# project_github.net
KiCad netlist of a schematic drawn in EAGLE
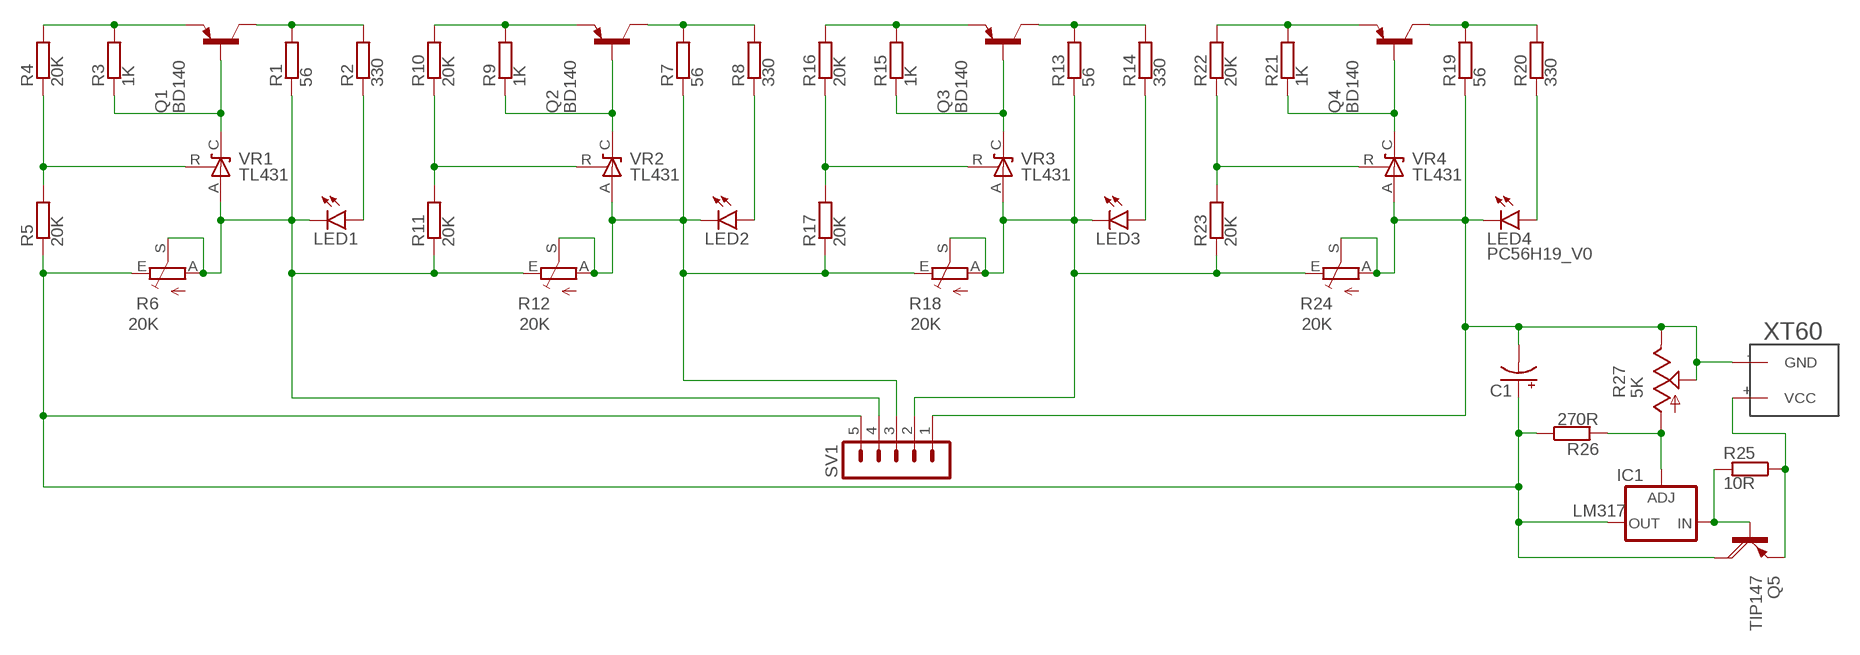
[diagram p0: schematic, sheet 1]

(export (version "E")
  (design (tool "Eeschema 10.0.6"))
  (components
    (comp (ref "C1")
      (value "CPOL-US153CLV-0810")
      (footprint "eagle-import:153CLV-0810")
      (libsource (lib "eagle-import") (part "CPOL-US153CLV-0810"))
    )
    (comp (ref "IC1")
      (value "LM317")
      (footprint "eagle-import:DPACK")
      (libsource (lib "eagle-import") (part "v-reg_409_LM317?MABDT"))
    )
    (comp (ref "LED1")
      (value "PC56H19_V0")
      (footprint "eagle-import:PC56H19_V0")
      (libsource (lib "eagle-import") (part "PC56H19_V0"))
    )
    (comp (ref "LED2")
      (value "PC56H19_V0")
      (footprint "eagle-import:PC56H19_V0")
      (libsource (lib "eagle-import") (part "PC56H19_V0"))
    )
    (comp (ref "LED3")
      (value "PC56H19_V0")
      (footprint "eagle-import:PC56H19_V0")
      (libsource (lib "eagle-import") (part "PC56H19_V0"))
    )
    (comp (ref "LED4")
      (value "PC56H19_V0")
      (footprint "eagle-import:PC56H19_V0")
      (libsource (lib "eagle-import") (part "PC56H19_V0"))
    )
    (comp (ref "Q1")
      (value "BD140")
      (footprint "eagle-import:TO126")
      (libsource (lib "eagle-import") (part "BD140"))
    )
    (comp (ref "Q2")
      (value "BD140")
      (footprint "eagle-import:TO126")
      (libsource (lib "eagle-import") (part "BD140"))
    )
    (comp (ref "Q3")
      (value "BD140")
      (footprint "eagle-import:TO126")
      (libsource (lib "eagle-import") (part "BD140"))
    )
    (comp (ref "Q4")
      (value "BD140")
      (footprint "eagle-import:TO126")
      (libsource (lib "eagle-import") (part "BD140"))
    )
    (comp (ref "Q5")
      (value "TIP147")
      (footprint "eagle-import:SOT93")
      (libsource (lib "eagle-import") (part "TIP147"))
    )
    (comp (ref "R1")
      (value "56")
      (footprint "eagle-import:SMK")
      (libsource (lib "eagle-import") (part "SMK"))
    )
    (comp (ref "R2")
      (value "330")
      (footprint "eagle-import:SMK")
      (libsource (lib "eagle-import") (part "SMK"))
    )
    (comp (ref "R3")
      (value "1K")
      (footprint "eagle-import:SMK")
      (libsource (lib "eagle-import") (part "SMK"))
    )
    (comp (ref "R4")
      (value "20K")
      (footprint "eagle-import:SMK")
      (libsource (lib "eagle-import") (part "SMK"))
    )
    (comp (ref "R5")
      (value "20K")
      (footprint "eagle-import:SMK")
      (libsource (lib "eagle-import") (part "SMK"))
    )
    (comp (ref "R6")
      (value "20K")
      (footprint "eagle-import:RJ9W")
      (libsource (lib "eagle-import") (part "TRIM_EU-RJ9W"))
    )
    (comp (ref "R7")
      (value "56")
      (footprint "eagle-import:SMK")
      (libsource (lib "eagle-import") (part "SMK"))
    )
    (comp (ref "R8")
      (value "330")
      (footprint "eagle-import:SMK")
      (libsource (lib "eagle-import") (part "SMK"))
    )
    (comp (ref "R9")
      (value "1K")
      (footprint "eagle-import:SMK")
      (libsource (lib "eagle-import") (part "SMK"))
    )
    (comp (ref "R10")
      (value "20K")
      (footprint "eagle-import:SMK")
      (libsource (lib "eagle-import") (part "SMK"))
    )
    (comp (ref "R11")
      (value "20K")
      (footprint "eagle-import:SMK")
      (libsource (lib "eagle-import") (part "SMK"))
    )
    (comp (ref "R12")
      (value "20K")
      (footprint "eagle-import:RJ9W")
      (libsource (lib "eagle-import") (part "TRIM_EU-RJ9W"))
    )
    (comp (ref "R13")
      (value "56")
      (footprint "eagle-import:SMK")
      (libsource (lib "eagle-import") (part "SMK"))
    )
    (comp (ref "R14")
      (value "330")
      (footprint "eagle-import:SMK")
      (libsource (lib "eagle-import") (part "SMK"))
    )
    (comp (ref "R15")
      (value "1K")
      (footprint "eagle-import:SMK")
      (libsource (lib "eagle-import") (part "SMK"))
    )
    (comp (ref "R16")
      (value "20K")
      (footprint "eagle-import:SMK")
      (libsource (lib "eagle-import") (part "SMK"))
    )
    (comp (ref "R17")
      (value "20K")
      (footprint "eagle-import:SMK")
      (libsource (lib "eagle-import") (part "SMK"))
    )
    (comp (ref "R18")
      (value "20K")
      (footprint "eagle-import:RJ9W")
      (libsource (lib "eagle-import") (part "TRIM_EU-RJ9W"))
    )
    (comp (ref "R19")
      (value "56")
      (footprint "eagle-import:SMK")
      (libsource (lib "eagle-import") (part "SMK"))
    )
    (comp (ref "R20")
      (value "330")
      (footprint "eagle-import:SMK")
      (libsource (lib "eagle-import") (part "SMK"))
    )
    (comp (ref "R21")
      (value "1K")
      (footprint "eagle-import:SMK")
      (libsource (lib "eagle-import") (part "SMK"))
    )
    (comp (ref "R22")
      (value "20K")
      (footprint "eagle-import:SMK")
      (libsource (lib "eagle-import") (part "SMK"))
    )
    (comp (ref "R23")
      (value "20K")
      (footprint "eagle-import:SMK")
      (libsource (lib "eagle-import") (part "SMK"))
    )
    (comp (ref "R24")
      (value "20K")
      (footprint "eagle-import:RJ9W")
      (libsource (lib "eagle-import") (part "TRIM_EU-RJ9W"))
    )
    (comp (ref "R25")
      (value "10R")
      (footprint "eagle-import:SMK")
      (libsource (lib "eagle-import") (part "SMK"))
    )
    (comp (ref "R26")
      (value "270R")
      (footprint "eagle-import:SMK")
      (libsource (lib "eagle-import") (part "SMK"))
    )
    (comp (ref "R27")
      (value "5K")
      (footprint "eagle-import:RJ9W")
      (libsource (lib "eagle-import") (part "TRIM_US-RJ9W"))
    )
    (comp (ref "SV1")
      (value "MA05-1")
      (footprint "eagle-import:MA05-1")
      (libsource (lib "eagle-import") (part "MA05-1"))
    )
    (comp (ref "U$1")
      (value "XT60")
      (footprint "eagle-import:XT60")
      (libsource (lib "eagle-import") (part "XT60"))
    )
    (comp (ref "VR1")
      (value "TL431")
      (footprint "eagle-import:TO-92_RAC")
      (libsource (lib "eagle-import") (part "TL431"))
    )
    (comp (ref "VR2")
      (value "TL431")
      (footprint "eagle-import:TO-92_RAC")
      (libsource (lib "eagle-import") (part "TL431"))
    )
    (comp (ref "VR3")
      (value "TL431")
      (footprint "eagle-import:TO-92_RAC")
      (libsource (lib "eagle-import") (part "TL431"))
    )
    (comp (ref "VR4")
      (value "TL431")
      (footprint "eagle-import:TO-92_RAC")
      (libsource (lib "eagle-import") (part "TL431"))
    )
  )
  (nets
    (net (code "1") (name "Net-(IC1-ADJ)") (class "Default")
      (node (ref "IC1") (pin "1") (pinfunction "ADJ_1") (pintype "input"))
      (node (ref "R26") (pin "2") (pinfunction "2_2") (pintype "passive"))
      (node (ref "R27") (pin "A") (pinfunction "A_A") (pintype "passive"))
    )
    (net (code "2") (name "Net-(IC1-IN)") (class "Default")
      (node (ref "IC1") (pin "3") (pinfunction "IN_3") (pintype "input"))
      (node (ref "Q5") (pin "B") (pinfunction "B_B") (pintype "passive"))
      (node (ref "R25") (pin "2") (pinfunction "2_2") (pintype "passive"))
    )
    (net (code "3") (name "Net-(IC1-OUT)") (class "Default")
      (node (ref "C1") (pin "+") (pinfunction "+_+") (pintype "passive"))
      (node (ref "IC1") (pin "4") (pinfunction "OUT_4") (pintype "passive"))
      (node (ref "Q5") (pin "C") (pinfunction "C_C") (pintype "passive"))
      (node (ref "R26") (pin "1") (pinfunction "1_1") (pintype "passive"))
      (node (ref "R5") (pin "2") (pinfunction "2_2") (pintype "passive"))
      (node (ref "R6") (pin "E") (pinfunction "E_E") (pintype "passive"))
      (node (ref "SV1") (pin "5") (pinfunction "5_5") (pintype "passive"))
    )
    (net (code "4") (name "Net-(LED1-A-Pad2)") (class "Default")
      (node (ref "LED1") (pin "2") (pinfunction "A_2") (pintype "passive"))
      (node (ref "LED1") (pin "4") (pinfunction "A_4") (pintype "passive"))
      (node (ref "R2") (pin "2") (pinfunction "2_2") (pintype "passive"))
    )
    (net (code "5") (name "Net-(LED1-C-Pad1)") (class "Default")
      (node (ref "LED1") (pin "1") (pinfunction "C_1") (pintype "passive"))
      (node (ref "LED1") (pin "3") (pinfunction "C_3") (pintype "passive"))
      (node (ref "R1") (pin "2") (pinfunction "2_2") (pintype "passive"))
      (node (ref "R11") (pin "2") (pinfunction "2_2") (pintype "passive"))
      (node (ref "R12") (pin "E") (pinfunction "E_E") (pintype "passive"))
      (node (ref "R6") (pin "A") (pinfunction "A_A") (pintype "passive"))
      (node (ref "R6") (pin "S") (pinfunction "S_S") (pintype "passive"))
      (node (ref "SV1") (pin "4") (pinfunction "4_4") (pintype "passive"))
      (node (ref "VR1") (pin "A") (pinfunction "A_A") (pintype "passive"))
    )
    (net (code "6") (name "Net-(LED2-A-Pad2)") (class "Default")
      (node (ref "LED2") (pin "2") (pinfunction "A_2") (pintype "passive"))
      (node (ref "LED2") (pin "4") (pinfunction "A_4") (pintype "passive"))
      (node (ref "R8") (pin "2") (pinfunction "2_2") (pintype "passive"))
    )
    (net (code "7") (name "Net-(LED2-C-Pad1)") (class "Default")
      (node (ref "LED2") (pin "1") (pinfunction "C_1") (pintype "passive"))
      (node (ref "LED2") (pin "3") (pinfunction "C_3") (pintype "passive"))
      (node (ref "R12") (pin "A") (pinfunction "A_A") (pintype "passive"))
      (node (ref "R12") (pin "S") (pinfunction "S_S") (pintype "passive"))
      (node (ref "R17") (pin "2") (pinfunction "2_2") (pintype "passive"))
      (node (ref "R18") (pin "E") (pinfunction "E_E") (pintype "passive"))
      (node (ref "R7") (pin "2") (pinfunction "2_2") (pintype "passive"))
      (node (ref "SV1") (pin "3") (pinfunction "3_3") (pintype "passive"))
      (node (ref "VR2") (pin "A") (pinfunction "A_A") (pintype "passive"))
    )
    (net (code "8") (name "Net-(LED3-A-Pad2)") (class "Default")
      (node (ref "LED3") (pin "2") (pinfunction "A_2") (pintype "passive"))
      (node (ref "LED3") (pin "4") (pinfunction "A_4") (pintype "passive"))
      (node (ref "R14") (pin "2") (pinfunction "2_2") (pintype "passive"))
    )
    (net (code "9") (name "Net-(LED3-C-Pad1)") (class "Default")
      (node (ref "LED3") (pin "1") (pinfunction "C_1") (pintype "passive"))
      (node (ref "LED3") (pin "3") (pinfunction "C_3") (pintype "passive"))
      (node (ref "R13") (pin "2") (pinfunction "2_2") (pintype "passive"))
      (node (ref "R18") (pin "A") (pinfunction "A_A") (pintype "passive"))
      (node (ref "R18") (pin "S") (pinfunction "S_S") (pintype "passive"))
      (node (ref "R23") (pin "2") (pinfunction "2_2") (pintype "passive"))
      (node (ref "R24") (pin "E") (pinfunction "E_E") (pintype "passive"))
      (node (ref "SV1") (pin "2") (pinfunction "2_2") (pintype "passive"))
      (node (ref "VR3") (pin "A") (pinfunction "A_A") (pintype "passive"))
    )
    (net (code "10") (name "Net-(LED4-A-Pad2)") (class "Default")
      (node (ref "LED4") (pin "2") (pinfunction "A_2") (pintype "passive"))
      (node (ref "LED4") (pin "4") (pinfunction "A_4") (pintype "passive"))
      (node (ref "R20") (pin "2") (pinfunction "2_2") (pintype "passive"))
    )
    (net (code "11") (name "Net-(Q1-B)") (class "Default")
      (node (ref "Q1") (pin "3") (pinfunction "B_3") (pintype "passive"))
      (node (ref "R3") (pin "2") (pinfunction "2_2") (pintype "passive"))
      (node (ref "VR1") (pin "C") (pinfunction "C_C") (pintype "passive"))
    )
    (net (code "12") (name "Net-(Q1-C)") (class "Default")
      (node (ref "Q1") (pin "2") (pinfunction "C_2") (pintype "passive"))
      (node (ref "R1") (pin "1") (pinfunction "1_1") (pintype "passive"))
      (node (ref "R2") (pin "1") (pinfunction "1_1") (pintype "passive"))
    )
    (net (code "13") (name "Net-(Q1-E)") (class "Default")
      (node (ref "Q1") (pin "1") (pinfunction "E_1") (pintype "passive"))
      (node (ref "R3") (pin "1") (pinfunction "1_1") (pintype "passive"))
      (node (ref "R4") (pin "1") (pinfunction "1_1") (pintype "passive"))
    )
    (net (code "14") (name "Net-(Q2-B)") (class "Default")
      (node (ref "Q2") (pin "3") (pinfunction "B_3") (pintype "passive"))
      (node (ref "R9") (pin "2") (pinfunction "2_2") (pintype "passive"))
      (node (ref "VR2") (pin "C") (pinfunction "C_C") (pintype "passive"))
    )
    (net (code "15") (name "Net-(Q2-C)") (class "Default")
      (node (ref "Q2") (pin "2") (pinfunction "C_2") (pintype "passive"))
      (node (ref "R7") (pin "1") (pinfunction "1_1") (pintype "passive"))
      (node (ref "R8") (pin "1") (pinfunction "1_1") (pintype "passive"))
    )
    (net (code "16") (name "Net-(Q2-E)") (class "Default")
      (node (ref "Q2") (pin "1") (pinfunction "E_1") (pintype "passive"))
      (node (ref "R10") (pin "1") (pinfunction "1_1") (pintype "passive"))
      (node (ref "R9") (pin "1") (pinfunction "1_1") (pintype "passive"))
    )
    (net (code "17") (name "Net-(Q3-B)") (class "Default")
      (node (ref "Q3") (pin "3") (pinfunction "B_3") (pintype "passive"))
      (node (ref "R15") (pin "2") (pinfunction "2_2") (pintype "passive"))
      (node (ref "VR3") (pin "C") (pinfunction "C_C") (pintype "passive"))
    )
    (net (code "18") (name "Net-(Q3-C)") (class "Default")
      (node (ref "Q3") (pin "2") (pinfunction "C_2") (pintype "passive"))
      (node (ref "R13") (pin "1") (pinfunction "1_1") (pintype "passive"))
      (node (ref "R14") (pin "1") (pinfunction "1_1") (pintype "passive"))
    )
    (net (code "19") (name "Net-(Q3-E)") (class "Default")
      (node (ref "Q3") (pin "1") (pinfunction "E_1") (pintype "passive"))
      (node (ref "R15") (pin "1") (pinfunction "1_1") (pintype "passive"))
      (node (ref "R16") (pin "1") (pinfunction "1_1") (pintype "passive"))
    )
    (net (code "20") (name "Net-(Q4-B)") (class "Default")
      (node (ref "Q4") (pin "3") (pinfunction "B_3") (pintype "passive"))
      (node (ref "R21") (pin "2") (pinfunction "2_2") (pintype "passive"))
      (node (ref "VR4") (pin "C") (pinfunction "C_C") (pintype "passive"))
    )
    (net (code "21") (name "Net-(Q4-C)") (class "Default")
      (node (ref "Q4") (pin "2") (pinfunction "C_2") (pintype "passive"))
      (node (ref "R19") (pin "1") (pinfunction "1_1") (pintype "passive"))
      (node (ref "R20") (pin "1") (pinfunction "1_1") (pintype "passive"))
    )
    (net (code "22") (name "Net-(Q4-E)") (class "Default")
      (node (ref "Q4") (pin "1") (pinfunction "E_1") (pintype "passive"))
      (node (ref "R21") (pin "1") (pinfunction "1_1") (pintype "passive"))
      (node (ref "R22") (pin "1") (pinfunction "1_1") (pintype "passive"))
    )
    (net (code "23") (name "Net-(R4-Pad2)") (class "Default")
      (node (ref "R4") (pin "2") (pinfunction "2_2") (pintype "passive"))
      (node (ref "R5") (pin "1") (pinfunction "1_1") (pintype "passive"))
      (node (ref "VR1") (pin "R") (pinfunction "R_R") (pintype "passive"))
    )
    (net (code "24") (name "Net-(R10-Pad2)") (class "Default")
      (node (ref "R10") (pin "2") (pinfunction "2_2") (pintype "passive"))
      (node (ref "R11") (pin "1") (pinfunction "1_1") (pintype "passive"))
      (node (ref "VR2") (pin "R") (pinfunction "R_R") (pintype "passive"))
    )
    (net (code "25") (name "Net-(R16-Pad2)") (class "Default")
      (node (ref "R16") (pin "2") (pinfunction "2_2") (pintype "passive"))
      (node (ref "R17") (pin "1") (pinfunction "1_1") (pintype "passive"))
      (node (ref "VR3") (pin "R") (pinfunction "R_R") (pintype "passive"))
    )
    (net (code "26") (name "Net-(R22-Pad2)") (class "Default")
      (node (ref "R22") (pin "2") (pinfunction "2_2") (pintype "passive"))
      (node (ref "R23") (pin "1") (pinfunction "1_1") (pintype "passive"))
      (node (ref "VR4") (pin "R") (pinfunction "R_R") (pintype "passive"))
    )
    (net (code "27") (name "Net-(U$1-GND)") (class "Default")
      (node (ref "C1") (pin "-") (pinfunction "-_-") (pintype "passive"))
      (node (ref "LED4") (pin "1") (pinfunction "C_1") (pintype "passive"))
      (node (ref "LED4") (pin "3") (pinfunction "C_3") (pintype "passive"))
      (node (ref "R19") (pin "2") (pinfunction "2_2") (pintype "passive"))
      (node (ref "R24") (pin "A") (pinfunction "A_A") (pintype "passive"))
      (node (ref "R24") (pin "S") (pinfunction "S_S") (pintype "passive"))
      (node (ref "R27") (pin "E") (pinfunction "E_E") (pintype "passive"))
      (node (ref "R27") (pin "S") (pinfunction "S_S") (pintype "passive"))
      (node (ref "SV1") (pin "1") (pinfunction "1_1") (pintype "passive"))
      (node (ref "U$1") (pin "-") (pinfunction "GND_-") (pintype "bidirectional"))
      (node (ref "VR4") (pin "A") (pinfunction "A_A") (pintype "passive"))
    )
    (net (code "28") (name "Net-(U$1-VCC)") (class "Default")
      (node (ref "Q5") (pin "E") (pinfunction "E_E") (pintype "passive"))
      (node (ref "R25") (pin "1") (pinfunction "1_1") (pintype "passive"))
      (node (ref "U$1") (pin "+") (pinfunction "VCC_+") (pintype "bidirectional"))
    )
  )
)
